# ToneController.net
KiCad netlist of a schematic drawn in Altium Designer
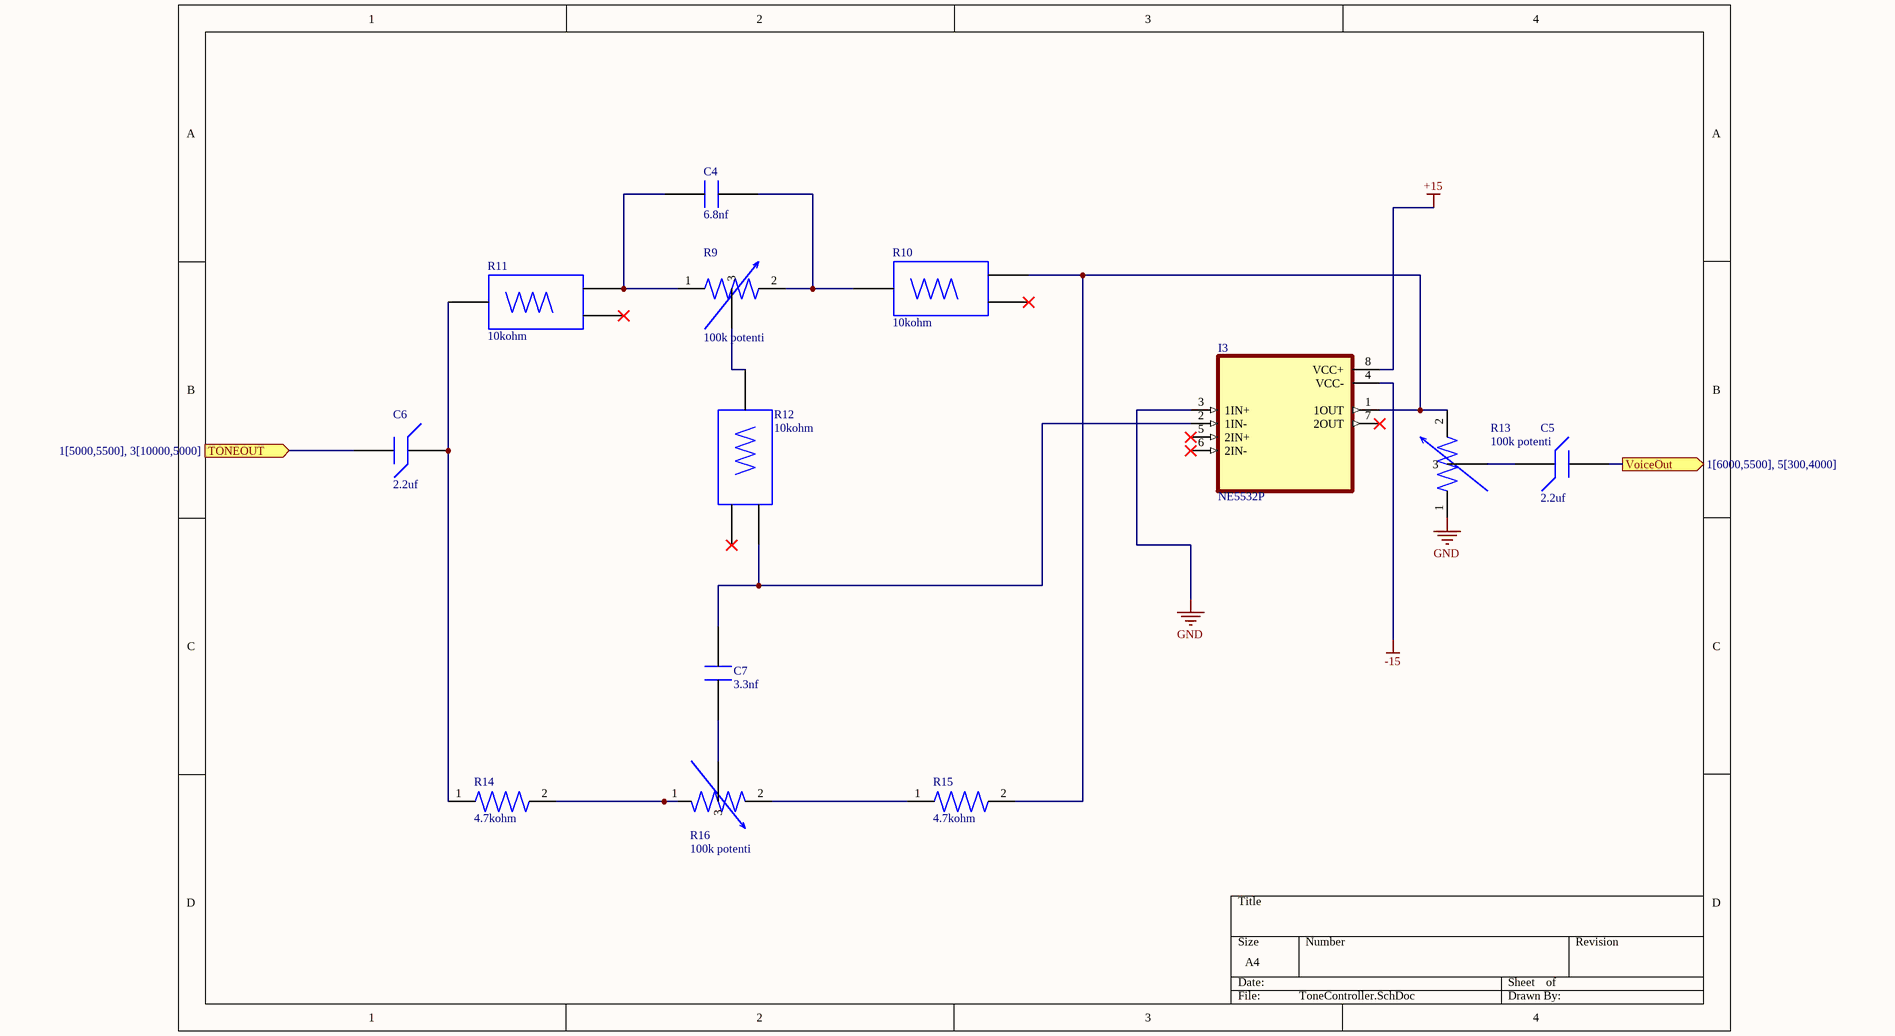
[diagram p0: ToneController.SchDoc]

(export (version "E")
  (design (tool "Eeschema 10.0.6"))
  (components
    (comp (ref "C4")
      (value "6.8nf")
      (footprint "ceramic Capacitor")
      (fields
        (field (name "MANUFACTURER") "KEMET")
        (field (name "MANUFACTURER PART NUMBER") "C781U682MZVDAAWL25")
      )
      (libsource (lib "AudioAmplifierBasic") (part "C781U682MZVDAAWL25"))
    )
    (comp (ref "C5")
      (value "2.2uf")
      (footprint "Capasitor")
      (fields
        (field (name "MANUFACTURER") "Rubycon")
        (field (name "MANUFACTURER PART NUMBER") "400LLE2R2MEFC8X11.5")
      )
      (libsource (lib "AudioAmplifierBasic") (part "400LLE2R2MEFC8X11.5"))
    )
    (comp (ref "C6")
      (value "2.2uf")
      (footprint "Capasitor")
      (fields
        (field (name "MANUFACTURER") "Rubycon")
        (field (name "MANUFACTURER PART NUMBER") "400LLE2R2MEFC8X11.5")
      )
      (libsource (lib "AudioAmplifierBasic") (part "400LLE2R2MEFC8X11.5"))
    )
    (comp (ref "C7")
      (value "3.3nf")
      (footprint "ceramic Capacitor")
      (fields
        (field (name "MANUFACTURER") "KEMET")
        (field (name "MANUFACTURER PART NUMBER") "C731U332MZVDBA7317")
      )
      (libsource (lib "AudioAmplifierBasic") (part "C731U332MZVDBA7317"))
    )
    (comp (ref "I3")
      (value "NE5532P")
      (footprint "NE5532P")
      (description "Operational Amplifier, 2 Func, 5000uV Offset-Max, BIPolar, PDIP8")
      (fields (field (name "MANUFACTURER") "Texas Instruments"))
      (libsource (lib "AudioAmplifierBasic") (part "NE5532P"))
    )
    (comp (ref "R9")
      (value "100k potenti")
      (footprint "Potentiometer - duplicate")
      (description "Potentiometer, Carbon, 0.08W, 100000ohm, 150V, 20% +/-Tol")
      (fields
        (field (name "MANUFACTURER") "Bourns")
        (field (name "MANUFACTURER PART NUMBER") "PDB12-H4251-104BF")
      )
      (libsource (lib "AudioAmplifierBasic") (part "PDB12-H4251-104BF"))
    )
    (comp (ref "R10")
      (value "10kohm")
      (footprint "10Kohm")
      (description "RES SMD 10K OHM 1% 35W TO263")
      (fields (field (name "MANUFACTURER") "Riedon") (field (name "MANUFACTURER PART NUMBER") "PFS35-10KF1"))
      (libsource (lib "AudioAmplifierBasic") (part "PFS35-10KF1"))
    )
    (comp (ref "R11")
      (value "10kohm")
      (footprint "10Kohm")
      (description "RES SMD 10K OHM 1% 35W TO263")
      (fields (field (name "MANUFACTURER") "Riedon") (field (name "MANUFACTURER PART NUMBER") "PFS35-10KF1"))
      (libsource (lib "AudioAmplifierBasic") (part "PFS35-10KF1"))
    )
    (comp (ref "R12")
      (value "10kohm")
      (footprint "10Kohm")
      (description "RES SMD 10K OHM 1% 35W TO263")
      (fields (field (name "MANUFACTURER") "Riedon") (field (name "MANUFACTURER PART NUMBER") "PFS35-10KF1"))
      (libsource (lib "AudioAmplifierBasic") (part "PFS35-10KF1"))
    )
    (comp (ref "R13")
      (value "100k potenti")
      (footprint "Potentiometer - duplicate")
      (description "Potentiometer, Carbon, 0.08W, 100000ohm, 150V, 20% +/-Tol")
      (fields
        (field (name "MANUFACTURER") "Bourns")
        (field (name "MANUFACTURER PART NUMBER") "PDB12-H4251-104BF")
      )
      (libsource (lib "AudioAmplifierBasic") (part "PDB12-H4251-104BF"))
    )
    (comp (ref "R14")
      (value "4.7kohm")
      (footprint "Resistor")
      (description "Fixed Resistor, Carbon Film, 0.125W, 4700ohm, 250V, 5% +/-Tol, -400,0ppm/Cel, Through Hole Mount")
      (fields
        (field (name "MANUFACTURER") "Stackpole Electronics")
        (field (name "MANUFACTURER PART NUMBER") "CF18JT4K70")
      )
      (libsource (lib "AudioAmplifierBasic") (part "CF18JT4K70"))
    )
    (comp (ref "R15")
      (value "4.7kohm")
      (footprint "Resistor")
      (description "Fixed Resistor, Carbon Film, 0.125W, 4700ohm, 250V, 5% +/-Tol, -400,0ppm/Cel, Through Hole Mount")
      (fields
        (field (name "MANUFACTURER") "Stackpole Electronics")
        (field (name "MANUFACTURER PART NUMBER") "CF18JT4K70")
      )
      (libsource (lib "AudioAmplifierBasic") (part "CF18JT4K70"))
    )
    (comp (ref "R16")
      (value "100k potenti")
      (footprint "Potentiometer - duplicate")
      (description "Potentiometer, Carbon, 0.08W, 100000ohm, 150V, 20% +/-Tol")
      (fields
        (field (name "MANUFACTURER") "Bourns")
        (field (name "MANUFACTURER PART NUMBER") "PDB12-H4251-104BF")
      )
      (libsource (lib "AudioAmplifierBasic") (part "PDB12-H4251-104BF"))
    )
  )
  (nets
    (net (code "1") (name "+15") (class "Default")
      (node (ref "I3") (pin "8") (pinfunction "VCC+_8") (pintype "power_in"))
    )
    (net (code "2") (name "-15") (class "Default")
      (node (ref "I3") (pin "4") (pinfunction "VCC-_4") (pintype "power_in"))
    )
    (net (code "3") (name "/TONEOUT") (class "Default")
      (node (ref "C6") (pin "1") (pinfunction "1_1") (pintype "passive"))
    )
    (net (code "4") (name "/VoiceOut") (class "Default")
      (node (ref "C5") (pin "1") (pinfunction "1_1") (pintype "passive"))
    )
    (net (code "5") (name "GND") (class "Default")
      (node (ref "I3") (pin "3") (pinfunction "1IN+_3") (pintype "input"))
      (node (ref "R13") (pin "1") (pinfunction "1_1") (pintype "passive"))
    )
    (net (code "6") (name "Net-(C4-6)") (class "Default")
      (node (ref "C4") (pin "1") (pinfunction "6_1") (pintype "passive"))
      (node (ref "R11") (pin "2") (pinfunction "17_2") (pintype "passive"))
      (node (ref "R9") (pin "1") (pinfunction "1_1") (pintype "passive"))
    )
    (net (code "7") (name "Net-(C4-7)") (class "Default")
      (node (ref "C4") (pin "2") (pinfunction "7_2") (pintype "passive"))
      (node (ref "R10") (pin "1") (pinfunction "16_1") (pintype "passive"))
      (node (ref "R9") (pin "2") (pinfunction "2_2") (pintype "passive"))
    )
    (net (code "8") (name "Net-(C5-Pad2)") (class "Default")
      (node (ref "C5") (pin "2") (pinfunction "2_2") (pintype "passive"))
      (node (ref "R13") (pin "3") (pinfunction "3_3") (pintype "passive"))
    )
    (net (code "9") (name "Net-(C7-Pad1)") (class "Default")
      (node (ref "C7") (pin "1") (pinfunction "1_1") (pintype "passive"))
      (node (ref "R16") (pin "3") (pinfunction "3_3") (pintype "passive"))
    )
    (net (code "10") (name "Net-(I3-1IN-)") (class "Default")
      (node (ref "C7") (pin "2") (pinfunction "2_2") (pintype "passive"))
      (node (ref "I3") (pin "2") (pinfunction "1IN-_2") (pintype "input"))
      (node (ref "R12") (pin "2") (pinfunction "17_2") (pintype "passive"))
    )
    (net (code "11") (name "Net-(I3-1OUT)") (class "Default")
      (node (ref "I3") (pin "1") (pinfunction "1OUT_1") (pintype "output"))
      (node (ref "R10") (pin "2") (pinfunction "17_2") (pintype "passive"))
      (node (ref "R13") (pin "2") (pinfunction "2_2") (pintype "passive"))
      (node (ref "R15") (pin "2") (pinfunction "2_2") (pintype "passive"))
    )
    (net (code "12") (name "Net-(R11-16)") (class "Default")
      (node (ref "C6") (pin "2") (pinfunction "2_2") (pintype "passive"))
      (node (ref "R11") (pin "1") (pinfunction "16_1") (pintype "passive"))
      (node (ref "R14") (pin "1") (pinfunction "1_1") (pintype "passive"))
    )
    (net (code "13") (name "Net-(R12-16)") (class "Default")
      (node (ref "R12") (pin "1") (pinfunction "16_1") (pintype "passive"))
      (node (ref "R9") (pin "3") (pinfunction "3_3") (pintype "passive"))
    )
    (net (code "14") (name "Net-(R14-Pad2)") (class "Default")
      (node (ref "R14") (pin "2") (pinfunction "2_2") (pintype "passive"))
      (node (ref "R16") (pin "1") (pinfunction "1_1") (pintype "passive"))
    )
    (net (code "15") (name "Net-(R15-Pad1)") (class "Default")
      (node (ref "R15") (pin "1") (pinfunction "1_1") (pintype "passive"))
      (node (ref "R16") (pin "2") (pinfunction "2_2") (pintype "passive"))
    )
    (net (code "16") (name "unconnected-(I3-2IN+-Pad5)") (class "Default")
      (node (ref "I3") (pin "5") (pinfunction "2IN+_5") (pintype "input+no_connect"))
    )
    (net (code "17") (name "unconnected-(I3-2IN--Pad6)") (class "Default")
      (node (ref "I3") (pin "6") (pinfunction "2IN-_6") (pintype "input+no_connect"))
    )
    (net (code "18") (name "unconnected-(I3-2OUT-Pad7)") (class "Default")
      (node (ref "I3") (pin "7") (pinfunction "2OUT_7") (pintype "output+no_connect"))
    )
    (net (code "19") (name "unconnected-(R10-Pad3)") (class "Default")
      (node (ref "R10") (pin "3") (pinfunction "3_3") (pintype "passive+no_connect"))
    )
    (net (code "20") (name "unconnected-(R11-Pad3)") (class "Default")
      (node (ref "R11") (pin "3") (pinfunction "3_3") (pintype "passive+no_connect"))
    )
    (net (code "21") (name "unconnected-(R12-Pad3)") (class "Default")
      (node (ref "R12") (pin "3") (pinfunction "3_3") (pintype "passive+no_connect"))
    )
  )
)
